# 12V_PCM.net
KiCad netlist of a schematic drawn in Altium Designer
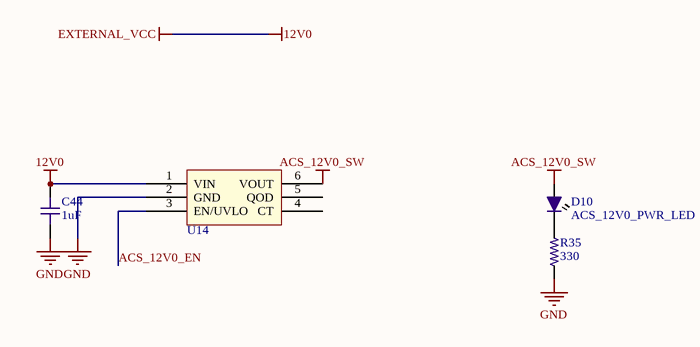
[diagram p0: 12V_PCM.SchDoc]

(export (version "E")
  (design (tool "Eeschema 10.0.6"))
  (components
    (comp (ref "C44")
      (value "1uF")
      (footprint "C0603-IPC")
      (description "Capacitor (0603)")
      (fields (field (name "Comment") "Capacitor"))
      (libsource (lib "UBC_Orbit_Shared_Components") (part "Capacitor"))
    )
    (comp (ref "D10")
      (value "ACS_12V0_PWR_LED")
      (footprint "LED0603-IPC")
      (description "Red PWR_LED")
      (libsource (lib "Diodes") (part "LED 0603 SMD"))
    )
    (comp (ref "R35")
      (value "330")
      (footprint "R0603-IPC")
      (description "Chip Resistor, 0603, 51hms, 0.1W")
      (fields (field (name "Comment") "0603 Template"))
      (libsource (lib "Resistors") (part "0603 Template"))
    )
    (comp (ref "U14")
      (value "One Channel Load Switch")
      (footprint "TPS22810-Q1")
      (description "2.7 - 18V @ 2A Max")
      (libsource (lib "Integrated_Circuits") (part "TPS22810-Q1"))
    )
  )
  (nets
    (net (code "1") (name "/ACS_12V0_EN") (class "Default")
      (node (ref "U14") (pin "3") (pinfunction "EN/UVLO_3") (pintype "passive"))
    )
    (net (code "2") (name "12V0") (class "Default")
      (node (ref "C44") (pin "2") (pintype "passive"))
      (node (ref "U14") (pin "1") (pinfunction "VIN_1") (pintype "passive"))
    )
    (net (code "3") (name "ACS_12V0_SW") (class "Default")
      (node (ref "D10") (pin "A") (pintype "passive"))
      (node (ref "U14") (pin "6") (pinfunction "VOUT_6") (pintype "passive"))
    )
    (net (code "4") (name "GND") (class "Default")
      (node (ref "C44") (pin "1") (pintype "passive"))
      (node (ref "R35") (pin "2") (pintype "passive"))
      (node (ref "U14") (pin "2") (pinfunction "GND_2") (pintype "passive"))
    )
    (net (code "5") (name "Net-(D10-PadK)") (class "Default")
      (node (ref "D10") (pin "K") (pintype "passive"))
      (node (ref "R35") (pin "1") (pintype "passive"))
    )
    (net (code "6") (name "unconnected-(U14-CT-Pad4)") (class "Default")
      (node (ref "U14") (pin "4") (pinfunction "CT_4") (pintype "passive"))
    )
    (net (code "7") (name "unconnected-(U14-QOD-Pad5)") (class "Default")
      (node (ref "U14") (pin "5") (pinfunction "QOD_5") (pintype "passive"))
    )
  )
)
